# LVBATTIND-MCU.net
KiCad netlist of a schematic drawn in Altium Designer
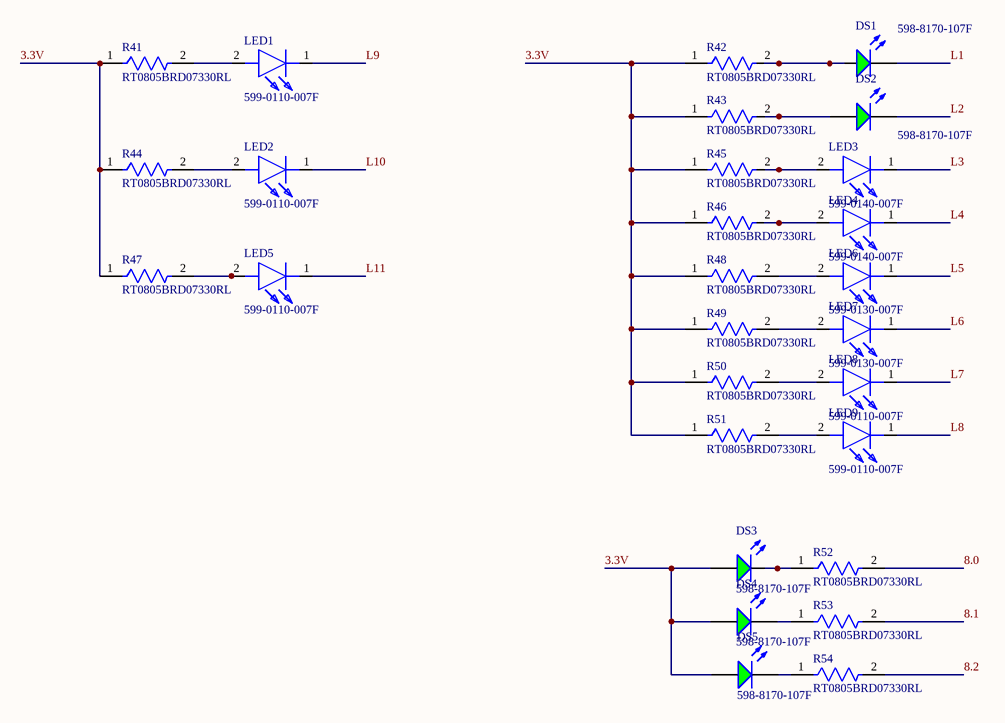
[diagram p0: LVBATTIND-MCU.SchDoc]

(export (version "E")
  (design (tool "Eeschema 10.0.6"))
  (components
    (comp (ref "DS1")
      (value "598-8170-107F")
      (footprint "DIAL-0805-2_V")
      (description "Single Color, 2 V, -30 to 85 degC, 2-Pin SMD (0805), RoHS, Tape and Reel")
      (libsource (lib "Altium Content Vault") (part "LED-GREEN-AK-2"))
    )
    (comp (ref "DS2")
      (value "598-8170-107F")
      (footprint "DIAL-0805-2_V")
      (description "Single Color, 2 V, -30 to 85 degC, 2-Pin SMD (0805), RoHS, Tape and Reel")
      (libsource (lib "Altium Content Vault") (part "LED-GREEN-AK-2"))
    )
    (comp (ref "DS3")
      (value "598-8170-107F")
      (footprint "DIAL-0805-2_V")
      (description "Single Color, 2 V, -30 to 85 degC, 2-Pin SMD (0805), RoHS, Tape and Reel")
      (libsource (lib "Altium Content Vault") (part "LED-GREEN-AK-2"))
    )
    (comp (ref "DS4")
      (value "598-8170-107F")
      (footprint "DIAL-0805-2_V")
      (description "Single Color, 2 V, -30 to 85 degC, 2-Pin SMD (0805), RoHS, Tape and Reel")
      (libsource (lib "Altium Content Vault") (part "LED-GREEN-AK-2"))
    )
    (comp (ref "DS5")
      (value "598-8170-107F")
      (footprint "DIAL-0805-2_V")
      (description "Single Color, 2 V, -30 to 85 degC, 2-Pin SMD (0805), RoHS, Tape and Reel")
      (libsource (lib "Altium Content Vault") (part "LED-GREEN-AK-2"))
    )
    (comp (ref "LED1")
      (value "599-0110-007F")
      (footprint "SamacSys:LEDM2012X90N")
      (description "LED")
      (fields (field (name "MOUSER PART NUMBER") "645-599-0110-007F"))
      (libsource (lib "*") (part "599-0110-007F"))
    )
    (comp (ref "LED2")
      (value "599-0110-007F")
      (footprint "SamacSys:LEDM2012X90N")
      (description "LED")
      (fields (field (name "MOUSER PART NUMBER") "645-599-0110-007F"))
      (libsource (lib "*") (part "599-0110-007F"))
    )
    (comp (ref "LED3")
      (value "599-0140-007F")
      (footprint "SamacSys:LEDC2012X70N")
      (description "LED")
      (fields (field (name "MOUSER PART NUMBER") "645-599-0140-007F"))
      (libsource (lib "*") (part "599-0140-007F"))
    )
    (comp (ref "LED4")
      (value "599-0140-007F")
      (footprint "SamacSys:LEDC2012X70N")
      (description "LED")
      (fields (field (name "MOUSER PART NUMBER") "645-599-0140-007F"))
      (libsource (lib "*") (part "599-0140-007F"))
    )
    (comp (ref "LED5")
      (value "599-0110-007F")
      (footprint "SamacSys:LEDM2012X90N")
      (description "LED")
      (fields (field (name "MOUSER PART NUMBER") "645-599-0110-007F"))
      (libsource (lib "*") (part "599-0110-007F"))
    )
    (comp (ref "LED6")
      (value "599-0130-007F")
      (footprint "SamacSys:5990130007F")
      (description "LED")
      (fields (field (name "MOUSER PART NUMBER") "645-599-0130-007F"))
      (libsource (lib "*") (part "599-0130-007F"))
    )
    (comp (ref "LED7")
      (value "599-0130-007F")
      (footprint "SamacSys:5990130007F")
      (description "LED")
      (fields (field (name "MOUSER PART NUMBER") "645-599-0130-007F"))
      (libsource (lib "*") (part "599-0130-007F"))
    )
    (comp (ref "LED8")
      (value "599-0110-007F")
      (footprint "SamacSys:LEDM2012X90N")
      (description "LED")
      (fields (field (name "MOUSER PART NUMBER") "645-599-0110-007F"))
      (libsource (lib "*") (part "599-0110-007F"))
    )
    (comp (ref "LED9")
      (value "599-0110-007F")
      (footprint "SamacSys:LEDM2012X90N")
      (description "LED")
      (fields (field (name "MOUSER PART NUMBER") "645-599-0110-007F"))
      (libsource (lib "*") (part "599-0110-007F"))
    )
    (comp (ref "R41")
      (value "RT0805BRD07330RL")
      (footprint "FP-RT0805-MFG")
      (description "RT0805 330Ω 0.125W 25 ppm/°C 0.25%")
      (fields (field (name "TOLERANCE") "0.0025"))
      (libsource (lib "Altium Content Vault") (part "1029c3af85768c4190bb7ad29bc67b5"))
    )
    (comp (ref "R42")
      (value "RT0805BRD07330RL")
      (footprint "FP-RT0805-MFG")
      (description "RT0805 330Ω 0.125W 25 ppm/°C 0.25%")
      (fields (field (name "TOLERANCE") "0.0025"))
      (libsource (lib "Altium Content Vault") (part "1029c3af85768c4190bb7ad29bc67b5"))
    )
    (comp (ref "R43")
      (value "RT0805BRD07330RL")
      (footprint "FP-RT0805-MFG")
      (description "RT0805 330Ω 0.125W 25 ppm/°C 0.25%")
      (fields (field (name "TOLERANCE") "0.0025"))
      (libsource (lib "Altium Content Vault") (part "1029c3af85768c4190bb7ad29bc67b5"))
    )
    (comp (ref "R44")
      (value "RT0805BRD07330RL")
      (footprint "FP-RT0805-MFG")
      (description "RT0805 330Ω 0.125W 25 ppm/°C 0.25%")
      (fields (field (name "TOLERANCE") "0.0025"))
      (libsource (lib "Altium Content Vault") (part "1029c3af85768c4190bb7ad29bc67b5"))
    )
    (comp (ref "R45")
      (value "RT0805BRD07330RL")
      (footprint "FP-RT0805-MFG")
      (description "RT0805 330Ω 0.125W 25 ppm/°C 0.25%")
      (fields (field (name "TOLERANCE") "0.0025"))
      (libsource (lib "Altium Content Vault") (part "1029c3af85768c4190bb7ad29bc67b5"))
    )
    (comp (ref "R46")
      (value "RT0805BRD07330RL")
      (footprint "FP-RT0805-MFG")
      (description "RT0805 330Ω 0.125W 25 ppm/°C 0.25%")
      (fields (field (name "TOLERANCE") "0.0025"))
      (libsource (lib "Altium Content Vault") (part "1029c3af85768c4190bb7ad29bc67b5"))
    )
    (comp (ref "R47")
      (value "RT0805BRD07330RL")
      (footprint "FP-RT0805-MFG")
      (description "RT0805 330Ω 0.125W 25 ppm/°C 0.25%")
      (fields (field (name "TOLERANCE") "0.0025"))
      (libsource (lib "Altium Content Vault") (part "1029c3af85768c4190bb7ad29bc67b5"))
    )
    (comp (ref "R48")
      (value "RT0805BRD07330RL")
      (footprint "FP-RT0805-MFG")
      (description "RT0805 330Ω 0.125W 25 ppm/°C 0.25%")
      (fields (field (name "TOLERANCE") "0.0025"))
      (libsource (lib "Altium Content Vault") (part "1029c3af85768c4190bb7ad29bc67b5"))
    )
    (comp (ref "R49")
      (value "RT0805BRD07330RL")
      (footprint "FP-RT0805-MFG")
      (description "RT0805 330Ω 0.125W 25 ppm/°C 0.25%")
      (fields (field (name "TOLERANCE") "0.0025"))
      (libsource (lib "Altium Content Vault") (part "1029c3af85768c4190bb7ad29bc67b5"))
    )
    (comp (ref "R50")
      (value "RT0805BRD07330RL")
      (footprint "FP-RT0805-MFG")
      (description "RT0805 330Ω 0.125W 25 ppm/°C 0.25%")
      (fields (field (name "TOLERANCE") "0.0025"))
      (libsource (lib "Altium Content Vault") (part "1029c3af85768c4190bb7ad29bc67b5"))
    )
    (comp (ref "R51")
      (value "RT0805BRD07330RL")
      (footprint "FP-RT0805-MFG")
      (description "RT0805 330Ω 0.125W 25 ppm/°C 0.25%")
      (fields (field (name "TOLERANCE") "0.0025"))
      (libsource (lib "Altium Content Vault") (part "1029c3af85768c4190bb7ad29bc67b5"))
    )
    (comp (ref "R52")
      (value "RT0805BRD07330RL")
      (footprint "FP-RT0805-MFG")
      (description "RT0805 330Ω 0.125W 25 ppm/°C 0.25%")
      (fields (field (name "TOLERANCE") "0.0025"))
      (libsource (lib "Altium Content Vault") (part "1029c3af85768c4190bb7ad29bc67b5"))
    )
    (comp (ref "R53")
      (value "RT0805BRD07330RL")
      (footprint "FP-RT0805-MFG")
      (description "RT0805 330Ω 0.125W 25 ppm/°C 0.25%")
      (fields (field (name "TOLERANCE") "0.0025"))
      (libsource (lib "Altium Content Vault") (part "1029c3af85768c4190bb7ad29bc67b5"))
    )
    (comp (ref "R54")
      (value "RT0805BRD07330RL")
      (footprint "FP-RT0805-MFG")
      (description "RT0805 330Ω 0.125W 25 ppm/°C 0.25%")
      (fields (field (name "TOLERANCE") "0.0025"))
      (libsource (lib "Altium Content Vault") (part "1029c3af85768c4190bb7ad29bc67b5"))
    )
  )
  (nets
    (net (code "1") (name "/3.3V") (class "Default")
      (node (ref "DS3") (pin "1") (pinfunction "A_1") (pintype "passive"))
      (node (ref "DS4") (pin "1") (pinfunction "A_1") (pintype "passive"))
      (node (ref "DS5") (pin "1") (pinfunction "A_1") (pintype "passive"))
      (node (ref "R41") (pin "1") (pinfunction "1_1") (pintype "passive"))
      (node (ref "R42") (pin "1") (pinfunction "1_1") (pintype "passive"))
      (node (ref "R43") (pin "1") (pinfunction "1_1") (pintype "passive"))
      (node (ref "R44") (pin "1") (pinfunction "1_1") (pintype "passive"))
      (node (ref "R45") (pin "1") (pinfunction "1_1") (pintype "passive"))
      (node (ref "R46") (pin "1") (pinfunction "1_1") (pintype "passive"))
      (node (ref "R47") (pin "1") (pinfunction "1_1") (pintype "passive"))
      (node (ref "R48") (pin "1") (pinfunction "1_1") (pintype "passive"))
      (node (ref "R49") (pin "1") (pinfunction "1_1") (pintype "passive"))
      (node (ref "R50") (pin "1") (pinfunction "1_1") (pintype "passive"))
      (node (ref "R51") (pin "1") (pinfunction "1_1") (pintype "passive"))
    )
    (net (code "2") (name "/8.0") (class "Default")
      (node (ref "R52") (pin "2") (pinfunction "2_2") (pintype "passive"))
    )
    (net (code "3") (name "/8.1") (class "Default")
      (node (ref "R53") (pin "2") (pinfunction "2_2") (pintype "passive"))
    )
    (net (code "4") (name "/8.2") (class "Default")
      (node (ref "R54") (pin "2") (pinfunction "2_2") (pintype "passive"))
    )
    (net (code "5") (name "/L1") (class "Default")
      (node (ref "DS1") (pin "2") (pinfunction "K_2") (pintype "passive"))
    )
    (net (code "6") (name "/L2") (class "Default")
      (node (ref "DS2") (pin "2") (pinfunction "K_2") (pintype "passive"))
    )
    (net (code "7") (name "/L3") (class "Default")
      (node (ref "LED3") (pin "1") (pinfunction "K_1") (pintype "passive"))
    )
    (net (code "8") (name "/L4") (class "Default")
      (node (ref "LED4") (pin "1") (pinfunction "K_1") (pintype "passive"))
    )
    (net (code "9") (name "/L5") (class "Default")
      (node (ref "LED6") (pin "1") (pinfunction "K_1") (pintype "passive"))
    )
    (net (code "10") (name "/L6") (class "Default")
      (node (ref "LED7") (pin "1") (pinfunction "K_1") (pintype "passive"))
    )
    (net (code "11") (name "/L7") (class "Default")
      (node (ref "LED8") (pin "1") (pinfunction "K_1") (pintype "passive"))
    )
    (net (code "12") (name "/L8") (class "Default")
      (node (ref "LED9") (pin "1") (pinfunction "K_1") (pintype "passive"))
    )
    (net (code "13") (name "/L9") (class "Default")
      (node (ref "LED1") (pin "1") (pinfunction "K_1") (pintype "passive"))
    )
    (net (code "14") (name "/L10") (class "Default")
      (node (ref "LED2") (pin "1") (pinfunction "K_1") (pintype "passive"))
    )
    (net (code "15") (name "/L11") (class "Default")
      (node (ref "LED5") (pin "1") (pinfunction "K_1") (pintype "passive"))
    )
    (net (code "16") (name "Net-(DS1-A)") (class "Default")
      (node (ref "DS1") (pin "1") (pinfunction "A_1") (pintype "passive"))
      (node (ref "R42") (pin "2") (pinfunction "2_2") (pintype "passive"))
    )
    (net (code "17") (name "Net-(DS2-A)") (class "Default")
      (node (ref "DS2") (pin "1") (pinfunction "A_1") (pintype "passive"))
      (node (ref "R43") (pin "2") (pinfunction "2_2") (pintype "passive"))
    )
    (net (code "18") (name "Net-(DS3-K)") (class "Default")
      (node (ref "DS3") (pin "2") (pinfunction "K_2") (pintype "passive"))
      (node (ref "R52") (pin "1") (pinfunction "1_1") (pintype "passive"))
    )
    (net (code "19") (name "Net-(DS4-K)") (class "Default")
      (node (ref "DS4") (pin "2") (pinfunction "K_2") (pintype "passive"))
      (node (ref "R53") (pin "1") (pinfunction "1_1") (pintype "passive"))
    )
    (net (code "20") (name "Net-(DS5-K)") (class "Default")
      (node (ref "DS5") (pin "2") (pinfunction "K_2") (pintype "passive"))
      (node (ref "R54") (pin "1") (pinfunction "1_1") (pintype "passive"))
    )
    (net (code "21") (name "Net-(LED1-A)") (class "Default")
      (node (ref "LED1") (pin "2") (pinfunction "A_2") (pintype "passive"))
      (node (ref "R41") (pin "2") (pinfunction "2_2") (pintype "passive"))
    )
    (net (code "22") (name "Net-(LED2-A)") (class "Default")
      (node (ref "LED2") (pin "2") (pinfunction "A_2") (pintype "passive"))
      (node (ref "R44") (pin "2") (pinfunction "2_2") (pintype "passive"))
    )
    (net (code "23") (name "Net-(LED3-A)") (class "Default")
      (node (ref "LED3") (pin "2") (pinfunction "A_2") (pintype "passive"))
      (node (ref "R45") (pin "2") (pinfunction "2_2") (pintype "passive"))
    )
    (net (code "24") (name "Net-(LED4-A)") (class "Default")
      (node (ref "LED4") (pin "2") (pinfunction "A_2") (pintype "passive"))
      (node (ref "R46") (pin "2") (pinfunction "2_2") (pintype "passive"))
    )
    (net (code "25") (name "Net-(LED5-A)") (class "Default")
      (node (ref "LED5") (pin "2") (pinfunction "A_2") (pintype "passive"))
      (node (ref "R47") (pin "2") (pinfunction "2_2") (pintype "passive"))
    )
    (net (code "26") (name "Net-(LED6-A)") (class "Default")
      (node (ref "LED6") (pin "2") (pinfunction "A_2") (pintype "passive"))
      (node (ref "R48") (pin "2") (pinfunction "2_2") (pintype "passive"))
    )
    (net (code "27") (name "Net-(LED7-A)") (class "Default")
      (node (ref "LED7") (pin "2") (pinfunction "A_2") (pintype "passive"))
      (node (ref "R49") (pin "2") (pinfunction "2_2") (pintype "passive"))
    )
    (net (code "28") (name "Net-(LED8-A)") (class "Default")
      (node (ref "LED8") (pin "2") (pinfunction "A_2") (pintype "passive"))
      (node (ref "R50") (pin "2") (pinfunction "2_2") (pintype "passive"))
    )
    (net (code "29") (name "Net-(LED9-A)") (class "Default")
      (node (ref "LED9") (pin "2") (pinfunction "A_2") (pintype "passive"))
      (node (ref "R51") (pin "2") (pinfunction "2_2") (pintype "passive"))
    )
  )
)
